# solderstation_v1_6.net
KiCad netlist of a schematic drawn in EAGLE
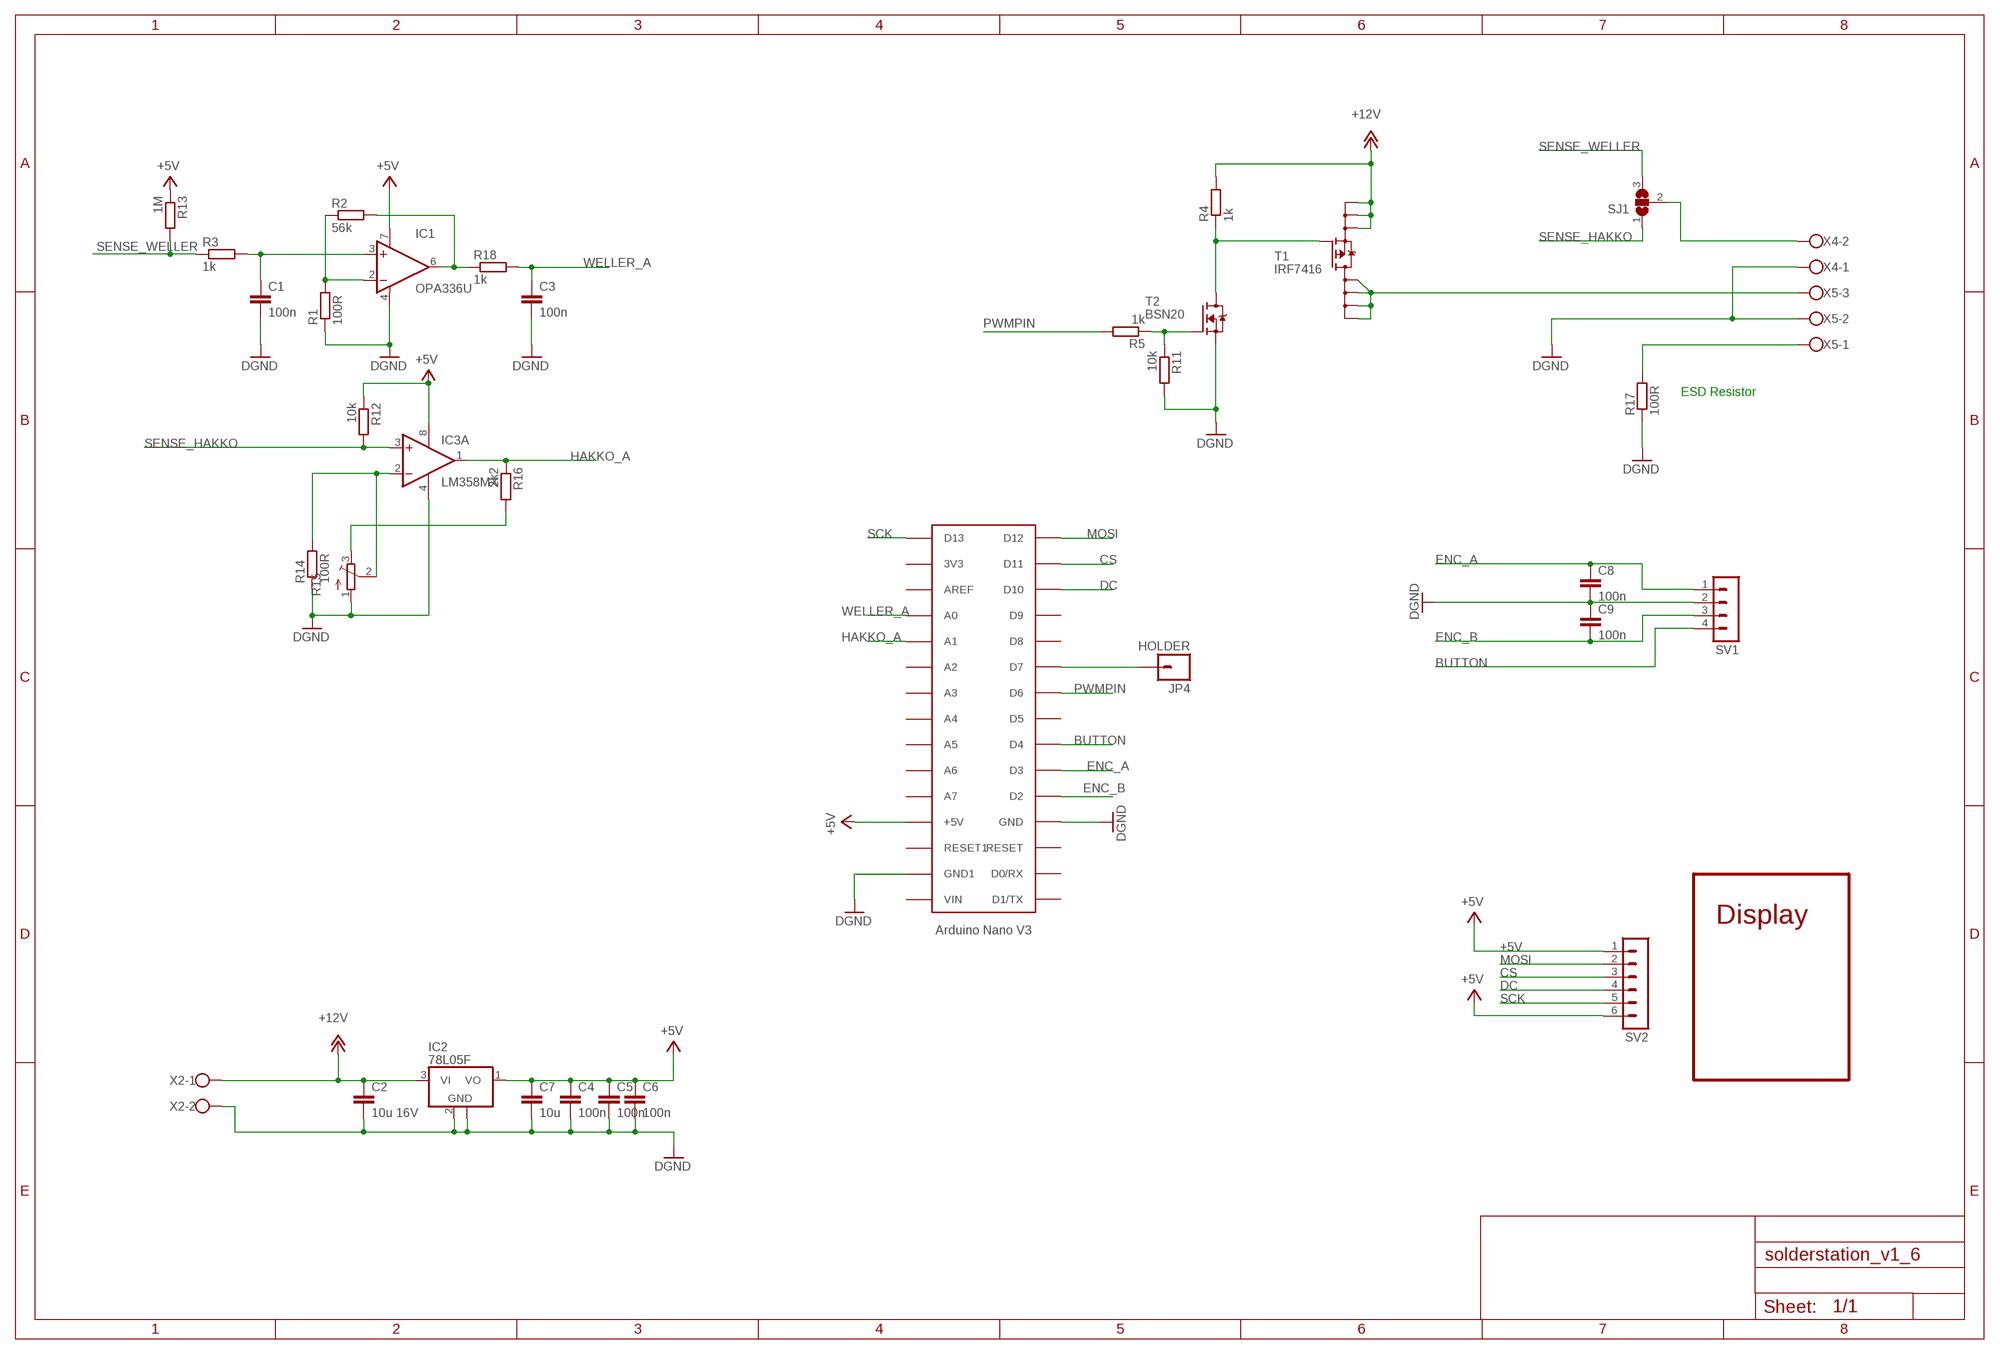
[diagram p0: schematic, sheet 1]

(export (version "E")
  (design (tool "Eeschema 10.0.6"))
  (components
    (comp (ref "C1")
      (value "100n")
      (footprint "eagle-import:C1206")
      (libsource (lib "eagle-import") (part "C-EUC1206"))
    )
    (comp (ref "C2")
      (value "10u 16V")
      (footprint "eagle-import:C1210K")
      (libsource (lib "eagle-import") (part "C-EUC1210K"))
    )
    (comp (ref "C3")
      (value "100n")
      (footprint "eagle-import:C1206")
      (libsource (lib "eagle-import") (part "C-EUC1206"))
    )
    (comp (ref "C4")
      (value "100n")
      (footprint "eagle-import:C1206")
      (libsource (lib "eagle-import") (part "C-EUC1206"))
    )
    (comp (ref "C5")
      (value "100n")
      (footprint "eagle-import:C1206")
      (libsource (lib "eagle-import") (part "C-EUC1206"))
    )
    (comp (ref "C6")
      (value "100n")
      (footprint "eagle-import:C1206")
      (libsource (lib "eagle-import") (part "C-EUC1206"))
    )
    (comp (ref "C7")
      (value "10u")
      (footprint "eagle-import:C1210K")
      (libsource (lib "eagle-import") (part "C-EUC1210K"))
    )
    (comp (ref "C8")
      (value "100n")
      (footprint "eagle-import:C1206")
      (libsource (lib "eagle-import") (part "C-EUC1206"))
    )
    (comp (ref "C9")
      (value "100n")
      (footprint "eagle-import:C1206")
      (libsource (lib "eagle-import") (part "C-EUC1206"))
    )
    (comp (ref "IC1")
      (value "OPA336U")
      (footprint "eagle-import:SO08")
      (fields (field (name "MF") "TEXAS INSTRUMENT CONNECTORS") (field (name "MPN") "OPA336UA"))
      (libsource (lib "eagle-import") (part "OPA336U"))
    )
    (comp (ref "IC2")
      (value "78L05F")
      (footprint "eagle-import:SOT89")
      (libsource (lib "eagle-import") (part "78LF05"))
    )
    (comp (ref "IC3")
      (value "LM358MX")
      (footprint "eagle-import:SO08")
      (libsource (lib "eagle-import") (part "LM358MX"))
    )
    (comp (ref "JP4")
      (value "HOLDER")
      (footprint "eagle-import:1X01")
      (libsource (lib "eagle-import") (part "M01PTH"))
    )
    (comp (ref "R1")
      (value "100R")
      (footprint "eagle-import:R0603")
      (libsource (lib "eagle-import") (part "R-EU_R0603"))
    )
    (comp (ref "R2")
      (value "56k")
      (footprint "eagle-import:R0603")
      (libsource (lib "eagle-import") (part "R-EU_R0603"))
    )
    (comp (ref "R3")
      (value "1k")
      (footprint "eagle-import:R0603")
      (libsource (lib "eagle-import") (part "R-EU_R0603"))
    )
    (comp (ref "R4")
      (value "1k")
      (footprint "eagle-import:R0603")
      (libsource (lib "eagle-import") (part "R-EU_R0603"))
    )
    (comp (ref "R5")
      (value "1k")
      (footprint "eagle-import:R0603")
      (libsource (lib "eagle-import") (part "R-EU_R0603"))
    )
    (comp (ref "R11")
      (value "10k")
      (footprint "eagle-import:R0603")
      (libsource (lib "eagle-import") (part "R-EU_R0603"))
    )
    (comp (ref "R12")
      (value "10k")
      (footprint "eagle-import:R0603")
      (libsource (lib "eagle-import") (part "R-EU_R0603"))
    )
    (comp (ref "R13")
      (value "1M")
      (footprint "eagle-import:R0603")
      (libsource (lib "eagle-import") (part "R-EU_R0603"))
    )
    (comp (ref "R14")
      (value "100R")
      (footprint "eagle-import:R0603")
      (libsource (lib "eagle-import") (part "R-EU_R0603"))
    )
    (comp (ref "R15")
      (value "TRIM_EU-SM-42/43X")
      (footprint "eagle-import:SM-42_43X")
      (libsource (lib "eagle-import") (part "TRIM_EU-SM-42/43X"))
    )
    (comp (ref "R16")
      (value "2k2")
      (footprint "eagle-import:R0603")
      (libsource (lib "eagle-import") (part "R-EU_R0603"))
    )
    (comp (ref "R17")
      (value "100R")
      (footprint "eagle-import:R0603")
      (libsource (lib "eagle-import") (part "R-EU_R0603"))
    )
    (comp (ref "R18")
      (value "1k")
      (footprint "eagle-import:R0603")
      (libsource (lib "eagle-import") (part "R-EU_R0603"))
    )
    (comp (ref "SJ1")
      (value "SJ2W")
      (footprint "eagle-import:SJ_2")
      (libsource (lib "eagle-import") (part "SJ2W"))
    )
    (comp (ref "SV1")
      (value "MA04-1")
      (footprint "eagle-import:MA04-1")
      (libsource (lib "eagle-import") (part "MA04-1"))
    )
    (comp (ref "SV2")
      (value "MA06-1")
      (footprint "eagle-import:MA06-1")
      (libsource (lib "eagle-import") (part "MA06-1"))
    )
    (comp (ref "T1")
      (value "IRF7416")
      (footprint "eagle-import:SO8")
      (libsource (lib "eagle-import") (part "IRF7416"))
    )
    (comp (ref "T2")
      (value "BSN20")
      (footprint "eagle-import:SOT23")
      (libsource (lib "eagle-import") (part "BSN20"))
    )
    (comp (ref "U$6")
      (value "ARDUINONANO")
      (footprint "eagle-import:PDIP-32")
      (libsource (lib "eagle-import") (part "ARDUINONANO"))
    )
    (comp (ref "X2")
      (value "W237-102")
      (footprint "eagle-import:W237-102")
      (fields (field (name "MPN") "237-102"))
      (libsource (lib "eagle-import") (part "W237-102"))
    )
    (comp (ref "X4")
      (value "W237-102")
      (footprint "eagle-import:W237-102")
      (fields (field (name "MPN") "237-102"))
      (libsource (lib "eagle-import") (part "W237-102"))
    )
    (comp (ref "X5")
      (value "W237-103")
      (footprint "eagle-import:W237-103")
      (fields (field (name "MPN") "237-103"))
      (libsource (lib "eagle-import") (part "W237-103"))
    )
  )
  (nets
    (net (code "1") (name "+5V") (class "Default")
      (node (ref "C4") (pin "1") (pinfunction "1_1") (pintype "passive"))
      (node (ref "C5") (pin "1") (pinfunction "1_1") (pintype "passive"))
      (node (ref "C6") (pin "1") (pinfunction "1_1") (pintype "passive"))
      (node (ref "C7") (pin "1") (pinfunction "1_1") (pintype "passive"))
      (node (ref "IC1") (pin "7") (pinfunction "V+_7") (pintype "power_in"))
      (node (ref "IC2") (pin "1") (pinfunction "VO_1") (pintype "passive"))
      (node (ref "IC3") (pin "8") (pinfunction "V+_8") (pintype "power_in"))
      (node (ref "R12") (pin "1") (pinfunction "1_1") (pintype "passive"))
      (node (ref "R13") (pin "1") (pinfunction "1_1") (pintype "passive"))
      (node (ref "SV2") (pin "1") (pinfunction "1_1") (pintype "passive"))
      (node (ref "SV2") (pin "6") (pinfunction "6_6") (pintype "passive"))
      (node (ref "U$6") (pin "+5V") (pinfunction "+5V_+5V") (pintype "bidirectional"))
    )
    (net (code "2") (name "+12V") (class "Default")
      (node (ref "C2") (pin "1") (pinfunction "1_1") (pintype "passive"))
      (node (ref "IC2") (pin "3") (pinfunction "VI_3") (pintype "input"))
      (node (ref "R4") (pin "2") (pinfunction "2_2") (pintype "passive"))
      (node (ref "T1") (pin "1") (pinfunction "S0_1") (pintype "passive"))
      (node (ref "T1") (pin "2") (pinfunction "S1_2") (pintype "passive"))
      (node (ref "T1") (pin "3") (pinfunction "S2_3") (pintype "passive"))
      (node (ref "X2") (pin "1") (pinfunction "KL_1") (pintype "passive"))
    )
    (net (code "3") (name "/BUTTON") (class "Default")
      (node (ref "SV1") (pin "4") (pinfunction "4_4") (pintype "passive"))
      (node (ref "U$6") (pin "D4") (pinfunction "D4_D4") (pintype "bidirectional"))
    )
    (net (code "4") (name "/CS") (class "Default")
      (node (ref "SV2") (pin "3") (pinfunction "3_3") (pintype "passive"))
      (node (ref "U$6") (pin "D11") (pinfunction "D11_D11") (pintype "bidirectional"))
    )
    (net (code "5") (name "/DC") (class "Default")
      (node (ref "SV2") (pin "4") (pinfunction "4_4") (pintype "passive"))
      (node (ref "U$6") (pin "D10") (pinfunction "D10_D10") (pintype "bidirectional"))
    )
    (net (code "6") (name "/ENC_A") (class "Default")
      (node (ref "C8") (pin "1") (pinfunction "1_1") (pintype "passive"))
      (node (ref "SV1") (pin "1") (pinfunction "1_1") (pintype "passive"))
      (node (ref "U$6") (pin "D3") (pinfunction "D3_D3") (pintype "bidirectional"))
    )
    (net (code "7") (name "/ENC_B") (class "Default")
      (node (ref "C9") (pin "2") (pinfunction "2_2") (pintype "passive"))
      (node (ref "SV1") (pin "3") (pinfunction "3_3") (pintype "passive"))
      (node (ref "U$6") (pin "D2") (pinfunction "D2_D2") (pintype "bidirectional"))
    )
    (net (code "8") (name "/HAKKO_A") (class "Default")
      (node (ref "IC3") (pin "1") (pinfunction "OUT_1") (pintype "output"))
      (node (ref "R16") (pin "1") (pinfunction "1_1") (pintype "passive"))
      (node (ref "U$6") (pin "A6") (pinfunction "A1_A6") (pintype "bidirectional"))
    )
    (net (code "9") (name "/MOSI") (class "Default")
      (node (ref "SV2") (pin "2") (pinfunction "2_2") (pintype "passive"))
      (node (ref "U$6") (pin "D12") (pinfunction "D12_D12") (pintype "bidirectional"))
    )
    (net (code "10") (name "/PWMPIN") (class "Default")
      (node (ref "R5") (pin "2") (pinfunction "2_2") (pintype "passive"))
      (node (ref "U$6") (pin "D6") (pinfunction "D6_D6") (pintype "bidirectional"))
    )
    (net (code "11") (name "/SCK") (class "Default")
      (node (ref "SV2") (pin "5") (pinfunction "5_5") (pintype "passive"))
      (node (ref "U$6") (pin "D13") (pinfunction "D13_D13") (pintype "bidirectional"))
    )
    (net (code "12") (name "/SENSE_HAKKO") (class "Default")
      (node (ref "IC3") (pin "3") (pinfunction "+IN_3") (pintype "input"))
      (node (ref "R12") (pin "2") (pinfunction "2_2") (pintype "passive"))
      (node (ref "SJ1") (pin "1") (pinfunction "1_1") (pintype "passive"))
    )
    (net (code "13") (name "/SENSE_WELLER") (class "Default")
      (node (ref "R13") (pin "2") (pinfunction "2_2") (pintype "passive"))
      (node (ref "R3") (pin "1") (pinfunction "1_1") (pintype "passive"))
      (node (ref "SJ1") (pin "3") (pinfunction "3_3") (pintype "passive"))
    )
    (net (code "14") (name "/WELLER_A") (class "Default")
      (node (ref "C3") (pin "1") (pinfunction "1_1") (pintype "passive"))
      (node (ref "R18") (pin "2") (pinfunction "2_2") (pintype "passive"))
      (node (ref "U$6") (pin "A7") (pinfunction "A0_A7") (pintype "bidirectional"))
    )
    (net (code "15") (name "DGND") (class "Default")
      (node (ref "C1") (pin "2") (pinfunction "2_2") (pintype "passive"))
      (node (ref "C2") (pin "2") (pinfunction "2_2") (pintype "passive"))
      (node (ref "C3") (pin "2") (pinfunction "2_2") (pintype "passive"))
      (node (ref "C4") (pin "2") (pinfunction "2_2") (pintype "passive"))
      (node (ref "C5") (pin "2") (pinfunction "2_2") (pintype "passive"))
      (node (ref "C6") (pin "2") (pinfunction "2_2") (pintype "passive"))
      (node (ref "C7") (pin "2") (pinfunction "2_2") (pintype "passive"))
      (node (ref "C8") (pin "2") (pinfunction "2_2") (pintype "passive"))
      (node (ref "C9") (pin "1") (pinfunction "1_1") (pintype "passive"))
      (node (ref "IC1") (pin "4") (pinfunction "V-_4") (pintype "power_in"))
      (node (ref "IC2") (pin "2") (pinfunction "GND_2") (pintype "passive"))
      (node (ref "IC2") (pin "2@1") (pinfunction "GND_2@1") (pintype "passive"))
      (node (ref "IC3") (pin "4") (pinfunction "V-_4") (pintype "power_in"))
      (node (ref "R1") (pin "1") (pinfunction "1_1") (pintype "passive"))
      (node (ref "R11") (pin "2") (pinfunction "2_2") (pintype "passive"))
      (node (ref "R14") (pin "1") (pinfunction "1_1") (pintype "passive"))
      (node (ref "R15") (pin "1") (pinfunction "A_1") (pintype "passive"))
      (node (ref "R17") (pin "1") (pinfunction "1_1") (pintype "passive"))
      (node (ref "SV1") (pin "2") (pinfunction "2_2") (pintype "passive"))
      (node (ref "T2") (pin "2") (pinfunction "S_2") (pintype "passive"))
      (node (ref "U$6") (pin "GND") (pinfunction "GND_GND") (pintype "bidirectional"))
      (node (ref "U$6") (pin "GND1") (pinfunction "GND1_GND1") (pintype "bidirectional"))
      (node (ref "X2") (pin "2") (pinfunction "KL_2") (pintype "passive"))
      (node (ref "X4") (pin "1") (pinfunction "KL_1") (pintype "passive"))
      (node (ref "X5") (pin "2") (pinfunction "KL_2") (pintype "passive"))
    )
    (net (code "16") (name "Net-(IC1-+IN)") (class "Default")
      (node (ref "C1") (pin "1") (pinfunction "1_1") (pintype "passive"))
      (node (ref "IC1") (pin "3") (pinfunction "+IN_3") (pintype "input"))
      (node (ref "R3") (pin "2") (pinfunction "2_2") (pintype "passive"))
    )
    (net (code "17") (name "Net-(IC1--IN)") (class "Default")
      (node (ref "IC1") (pin "2") (pinfunction "-IN_2") (pintype "input"))
      (node (ref "R1") (pin "2") (pinfunction "2_2") (pintype "passive"))
      (node (ref "R2") (pin "1") (pinfunction "1_1") (pintype "passive"))
    )
    (net (code "18") (name "Net-(IC1-OUT)") (class "Default")
      (node (ref "IC1") (pin "6") (pinfunction "OUT_6") (pintype "output"))
      (node (ref "R18") (pin "1") (pinfunction "1_1") (pintype "passive"))
      (node (ref "R2") (pin "2") (pinfunction "2_2") (pintype "passive"))
    )
    (net (code "19") (name "Net-(IC3A--IN)") (class "Default")
      (node (ref "IC3") (pin "2") (pinfunction "-IN_2") (pintype "input"))
      (node (ref "R14") (pin "2") (pinfunction "2_2") (pintype "passive"))
      (node (ref "R15") (pin "2") (pinfunction "S_2") (pintype "passive"))
    )
    (net (code "20") (name "Net-(JP4-Pad1)") (class "Default")
      (node (ref "JP4") (pin "1") (pinfunction "1_1") (pintype "passive"))
      (node (ref "U$6") (pin "D7") (pinfunction "D7_D7") (pintype "bidirectional"))
    )
    (net (code "21") (name "Net-(R15-E)") (class "Default")
      (node (ref "R15") (pin "3") (pinfunction "E_3") (pintype "passive"))
      (node (ref "R16") (pin "2") (pinfunction "2_2") (pintype "passive"))
    )
    (net (code "22") (name "Net-(T1-D0)") (class "Default")
      (node (ref "T1") (pin "5") (pinfunction "D0_5") (pintype "passive"))
      (node (ref "T1") (pin "6") (pinfunction "D1_6") (pintype "passive"))
      (node (ref "T1") (pin "7") (pinfunction "D2_7") (pintype "passive"))
      (node (ref "T1") (pin "8") (pinfunction "D3_8") (pintype "passive"))
      (node (ref "X5") (pin "3") (pinfunction "KL_3") (pintype "passive"))
    )
    (net (code "23") (name "Net-(T1-G)") (class "Default")
      (node (ref "R4") (pin "1") (pinfunction "1_1") (pintype "passive"))
      (node (ref "T1") (pin "4") (pinfunction "G_4") (pintype "passive"))
      (node (ref "T2") (pin "3") (pinfunction "D_3") (pintype "passive"))
    )
    (net (code "24") (name "Net-(T2-G)") (class "Default")
      (node (ref "R11") (pin "1") (pinfunction "1_1") (pintype "passive"))
      (node (ref "R5") (pin "1") (pinfunction "1_1") (pintype "passive"))
      (node (ref "T2") (pin "1") (pinfunction "G_1") (pintype "passive"))
    )
    (net (code "25") (name "Net-(X4B-KL)") (class "Default")
      (node (ref "SJ1") (pin "2") (pinfunction "2_2") (pintype "passive"))
      (node (ref "X4") (pin "2") (pinfunction "KL_2") (pintype "passive"))
    )
    (net (code "26") (name "Net-(X5A-KL)") (class "Default")
      (node (ref "R17") (pin "2") (pinfunction "2_2") (pintype "passive"))
      (node (ref "X5") (pin "1") (pinfunction "KL_1") (pintype "passive"))
    )
    (net (code "27") (name "unconnected-(U$6-A2-PadA5)") (class "Default")
      (node (ref "U$6") (pin "A5") (pinfunction "A2_A5") (pintype "bidirectional"))
    )
    (net (code "28") (name "unconnected-(U$6-A3-PadA4)") (class "Default")
      (node (ref "U$6") (pin "A4") (pinfunction "A3_A4") (pintype "bidirectional"))
    )
    (net (code "29") (name "unconnected-(U$6-A4-PadA3)") (class "Default")
      (node (ref "U$6") (pin "A3") (pinfunction "A4_A3") (pintype "bidirectional"))
    )
    (net (code "30") (name "unconnected-(U$6-A5-PadA2)") (class "Default")
      (node (ref "U$6") (pin "A2") (pinfunction "A5_A2") (pintype "bidirectional"))
    )
    (net (code "31") (name "unconnected-(U$6-A6-PadA1)") (class "Default")
      (node (ref "U$6") (pin "A1") (pinfunction "A6_A1") (pintype "bidirectional"))
    )
    (net (code "32") (name "unconnected-(U$6-A7-PadA0)") (class "Default")
      (node (ref "U$6") (pin "A0") (pinfunction "A7_A0") (pintype "bidirectional"))
    )
    (net (code "33") (name "unconnected-(U$6-Pad3V3)") (class "Default")
      (node (ref "U$6") (pin "3V3") (pinfunction "3V3_3V3") (pintype "bidirectional"))
    )
    (net (code "34") (name "unconnected-(U$6-PadAREF)") (class "Default")
      (node (ref "U$6") (pin "AREF") (pinfunction "AREF_AREF") (pintype "bidirectional"))
    )
    (net (code "35") (name "unconnected-(U$6-PadD0{slash}RX)") (class "Default")
      (node (ref "U$6") (pin "D0/RX") (pinfunction "D0/RX_D0/RX") (pintype "bidirectional"))
    )
    (net (code "36") (name "unconnected-(U$6-PadD1{slash}TX)") (class "Default")
      (node (ref "U$6") (pin "D1/TX") (pinfunction "D1/TX_D1/TX") (pintype "bidirectional"))
    )
    (net (code "37") (name "unconnected-(U$6-PadD5)") (class "Default")
      (node (ref "U$6") (pin "D5") (pinfunction "D5_D5") (pintype "bidirectional"))
    )
    (net (code "38") (name "unconnected-(U$6-PadD8)") (class "Default")
      (node (ref "U$6") (pin "D8") (pinfunction "D8_D8") (pintype "bidirectional"))
    )
    (net (code "39") (name "unconnected-(U$6-PadD9)") (class "Default")
      (node (ref "U$6") (pin "D9") (pinfunction "D9_D9") (pintype "bidirectional"))
    )
    (net (code "40") (name "unconnected-(U$6-PadRESET)") (class "Default")
      (node (ref "U$6") (pin "RESET") (pinfunction "RESET_RESET") (pintype "bidirectional"))
    )
    (net (code "41") (name "unconnected-(U$6-PadRESET1)") (class "Default")
      (node (ref "U$6") (pin "RESET1") (pinfunction "RESET1_RESET1") (pintype "bidirectional"))
    )
    (net (code "42") (name "unconnected-(U$6-PadVIN)") (class "Default")
      (node (ref "U$6") (pin "VIN") (pinfunction "VIN_VIN") (pintype "bidirectional"))
    )
  )
)
